# Sheet2.net
KiCad netlist of a schematic drawn in Altium Designer
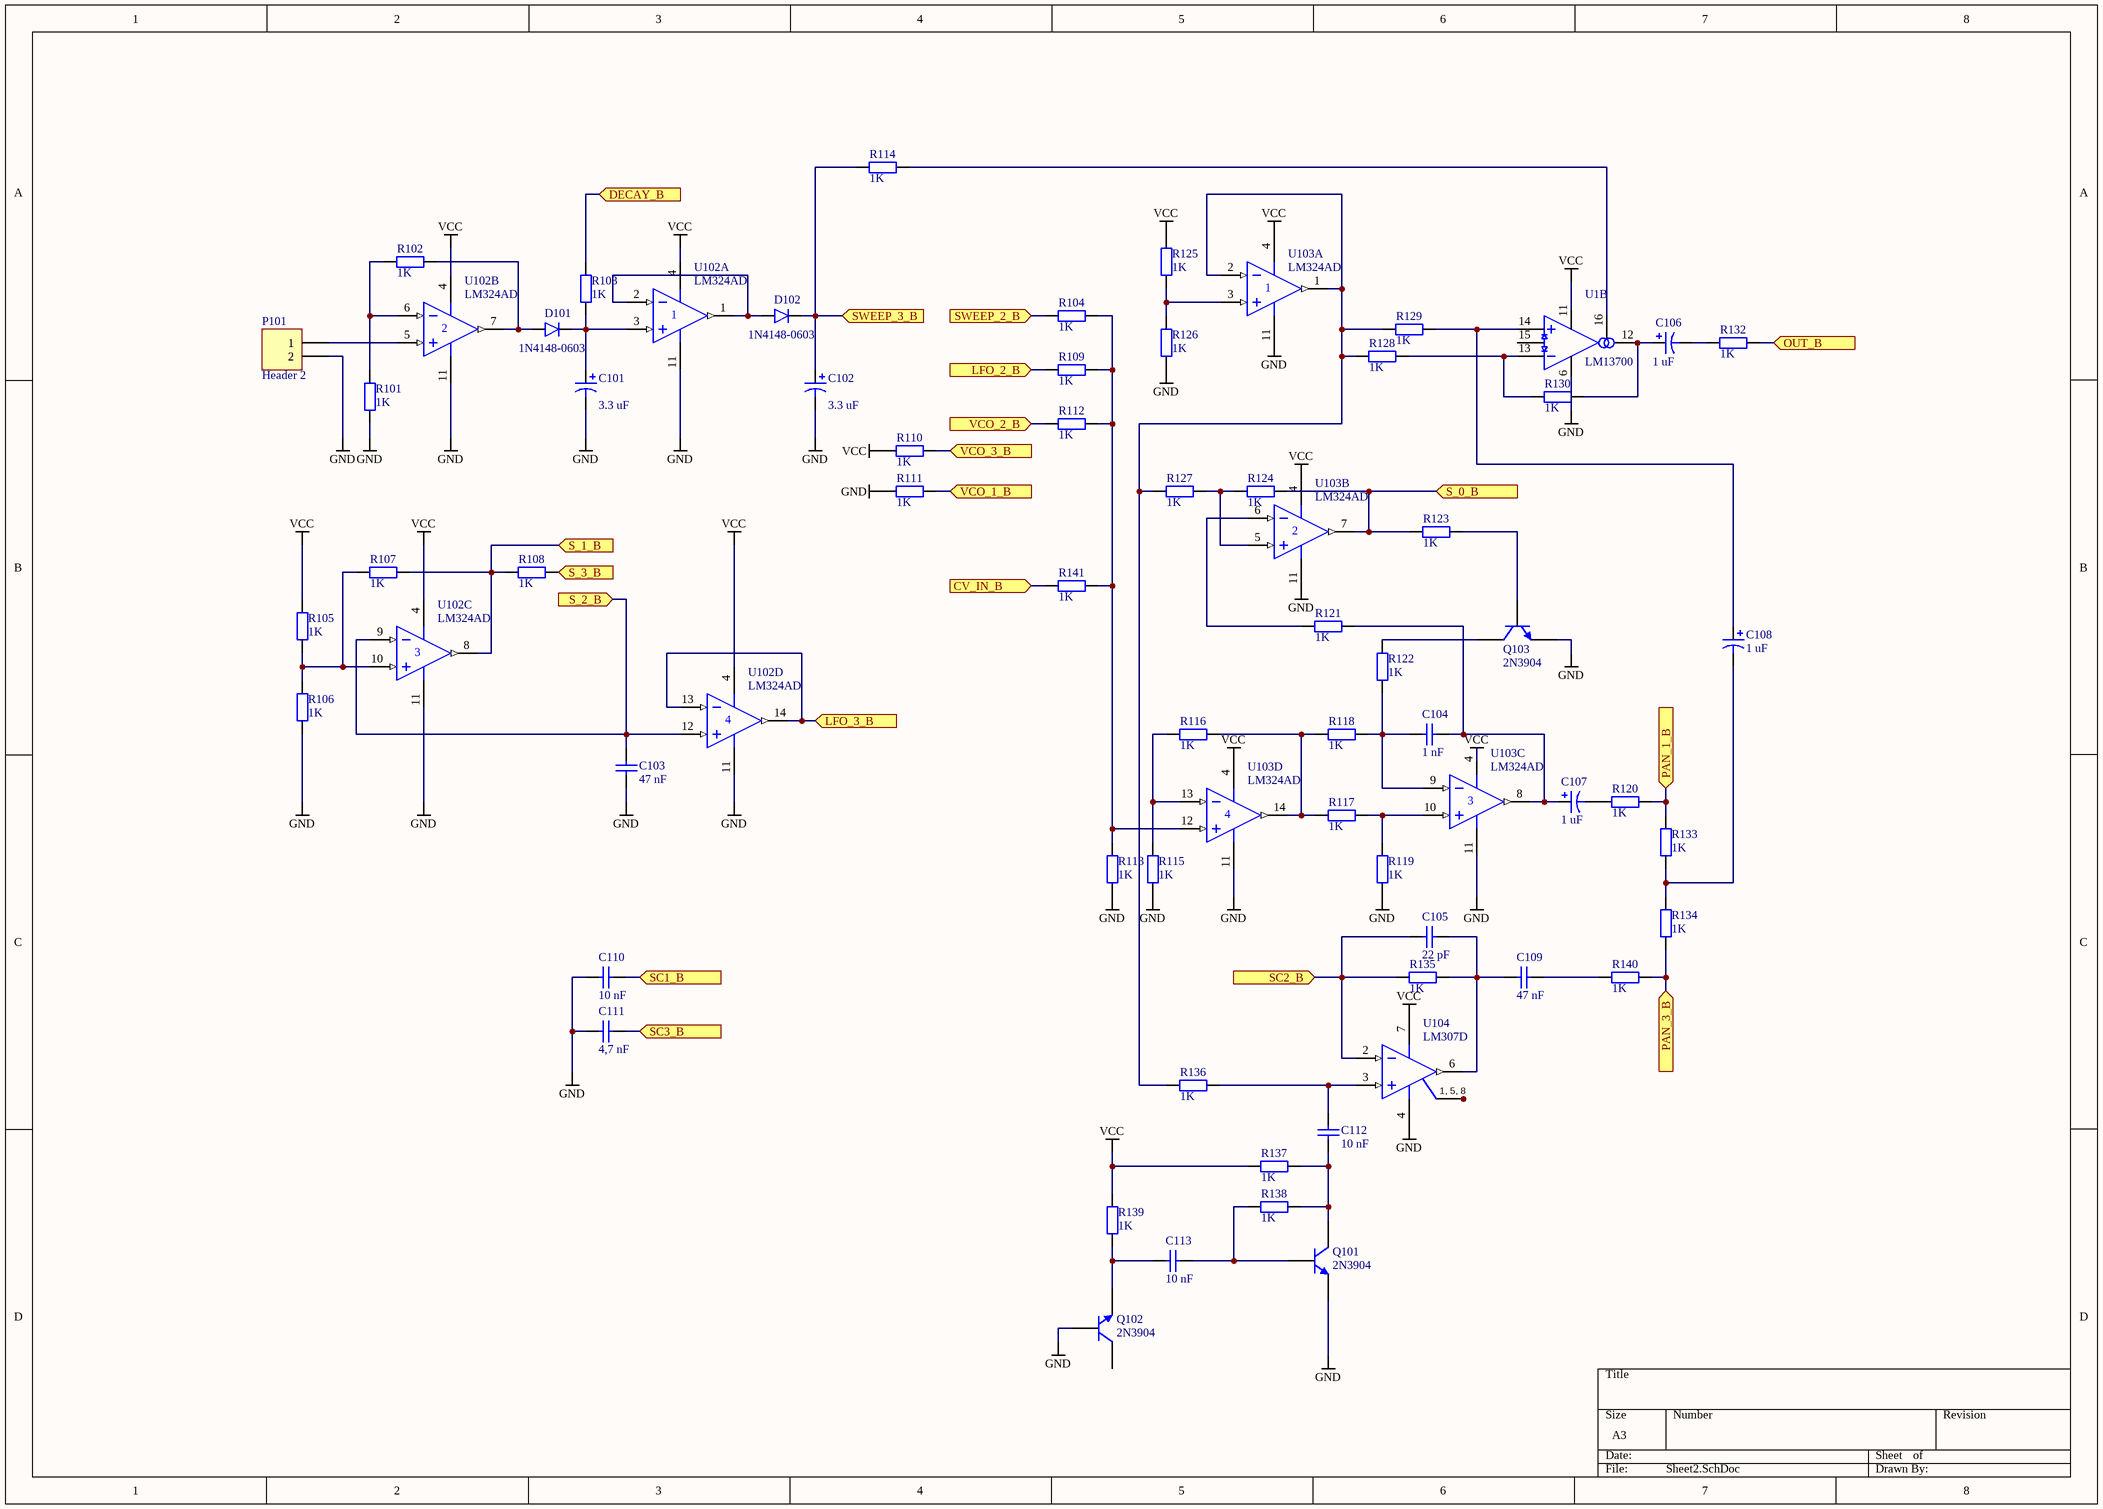
[diagram p0: Sheet2.SchDoc]

(export (version "E")
  (design (tool "Eeschema 10.0.6"))
  (components
    (comp (ref "C101")
      (value "3.3 uF")
      (footprint "C1206")
      (description "Polarized Capacitor (Radial)")
      (fields (field (name "Comment") "Cap Pol1") (field (name "PUBLISHER") "Altium Limited"))
      (libsource (lib "Miscellaneous Devices") (part "Cap Pol1"))
    )
    (comp (ref "C102")
      (value "3.3 uF")
      (footprint "C1206")
      (description "Polarized Capacitor (Radial)")
      (fields (field (name "Comment") "Cap Pol1") (field (name "PUBLISHER") "Altium Limited"))
      (libsource (lib "Miscellaneous Devices") (part "Cap Pol1"))
    )
    (comp (ref "C103")
      (value "47 nF")
      (footprint "C1206")
      (description "Capacitor")
      (fields (field (name "Comment") "Cap") (field (name "PUBLISHER") "Altium Limited"))
      (libsource (lib "Miscellaneous Devices") (part "Cap"))
    )
    (comp (ref "C104")
      (value "1 nF")
      (footprint "C1206")
      (description "Capacitor")
      (fields (field (name "Comment") "Cap") (field (name "PUBLISHER") "Altium Limited"))
      (libsource (lib "Miscellaneous Devices") (part "Cap"))
    )
    (comp (ref "C105")
      (value "22 pF")
      (footprint "C1206")
      (description "Capacitor")
      (fields (field (name "Comment") "Cap") (field (name "PUBLISHER") "Altium Limited"))
      (libsource (lib "Miscellaneous Devices") (part "Cap"))
    )
    (comp (ref "C106")
      (value "1 uF")
      (footprint "C1206")
      (description "Polarized Capacitor (Radial)")
      (fields (field (name "Comment") "Cap Pol1") (field (name "PUBLISHER") "Altium Limited"))
      (libsource (lib "Miscellaneous Devices") (part "Cap Pol1"))
    )
    (comp (ref "C107")
      (value "1 uF")
      (footprint "C1206")
      (description "Polarized Capacitor (Radial)")
      (fields (field (name "Comment") "Cap Pol1") (field (name "PUBLISHER") "Altium Limited"))
      (libsource (lib "Miscellaneous Devices") (part "Cap Pol1"))
    )
    (comp (ref "C108")
      (value "1 uF")
      (footprint "C1206")
      (description "Polarized Capacitor (Radial)")
      (fields (field (name "Comment") "Cap Pol1") (field (name "PUBLISHER") "Altium Limited"))
      (libsource (lib "Miscellaneous Devices") (part "Cap Pol1"))
    )
    (comp (ref "C109")
      (value "47 nF")
      (footprint "C1206")
      (description "Capacitor")
      (fields (field (name "Comment") "Cap") (field (name "PUBLISHER") "Altium Limited"))
      (libsource (lib "Miscellaneous Devices") (part "Cap"))
    )
    (comp (ref "C110")
      (value "10 nF")
      (footprint "C1206")
      (description "Capacitor")
      (fields (field (name "Comment") "Cap") (field (name "PUBLISHER") "Altium Limited"))
      (libsource (lib "Miscellaneous Devices") (part "Cap"))
    )
    (comp (ref "C111")
      (value "4,7 nF")
      (footprint "C1206")
      (description "Capacitor")
      (fields (field (name "Comment") "Cap") (field (name "PUBLISHER") "Altium Limited"))
      (libsource (lib "Miscellaneous Devices") (part "Cap"))
    )
    (comp (ref "C112")
      (value "10 nF")
      (footprint "C1206")
      (description "Capacitor")
      (fields (field (name "Comment") "Cap") (field (name "PUBLISHER") "Altium Limited"))
      (libsource (lib "Miscellaneous Devices") (part "Cap"))
    )
    (comp (ref "C113")
      (value "10 nF")
      (footprint "C1206")
      (description "Capacitor")
      (fields (field (name "Comment") "Cap") (field (name "PUBLISHER") "Altium Limited"))
      (libsource (lib "Miscellaneous Devices") (part "Cap"))
    )
    (comp (ref "D101")
      (value "1N4148-0603")
      (footprint "D0603")
      (description "Dioda: przełączająca; SMD; 100V; 150mA; 4ns; 0603")
      (libsource (lib "Component Library 3.0") (part "1N4148"))
    )
    (comp (ref "D102")
      (value "1N4148-0603")
      (footprint "D0603")
      (description "Dioda: przełączająca; SMD; 100V; 150mA; 4ns; 0603")
      (libsource (lib "Component Library 3.0") (part "1N4148"))
    )
    (comp (ref "P101")
      (value "Header 2")
      (footprint "HDR1X2")
      (description "Header, 2-Pin")
      (fields (field (name "PUBLISHER") "Altium Limited"))
      (libsource (lib "Miscellaneous Connectors") (part "Header 2"))
    )
    (comp (ref "Q101")
      (value "2N3904")
      (footprint "TO-92A")
      (description "NPN General Purpose Amplifier")
      (fields (field (name "PUBLISHER") "Altium Limited"))
      (libsource (lib "Miscellaneous Devices") (part "2N3904"))
    )
    (comp (ref "Q102")
      (value "2N3904")
      (footprint "TO-92A")
      (description "NPN General Purpose Amplifier")
      (fields (field (name "PUBLISHER") "Altium Limited"))
      (libsource (lib "Miscellaneous Devices") (part "2N3904"))
    )
    (comp (ref "Q103")
      (value "2N3904")
      (footprint "TO-92A")
      (description "NPN General Purpose Amplifier")
      (fields (field (name "PUBLISHER") "Altium Limited"))
      (libsource (lib "Miscellaneous Devices") (part "2N3904"))
    )
    (comp (ref "R101")
      (value "1K")
      (footprint "R1206")
      (description "Resistor")
      (fields (field (name "Comment") "Res2") (field (name "PUBLISHER") "Altium Limited"))
      (libsource (lib "Miscellaneous Devices") (part "Res2"))
    )
    (comp (ref "R102")
      (value "1K")
      (footprint "R1206")
      (description "Resistor")
      (fields (field (name "Comment") "Res2") (field (name "PUBLISHER") "Altium Limited"))
      (libsource (lib "") (part "Res2_1"))
    )
    (comp (ref "R103")
      (value "1K")
      (footprint "R1206")
      (description "Resistor")
      (fields (field (name "Comment") "Res2") (field (name "PUBLISHER") "Altium Limited"))
      (libsource (lib "") (part "Res2_3"))
    )
    (comp (ref "R104")
      (value "1K")
      (footprint "R1206")
      (description "Resistor")
      (fields (field (name "Comment") "Res2") (field (name "PUBLISHER") "Altium Limited"))
      (libsource (lib "") (part "Res2_2"))
    )
    (comp (ref "R105")
      (value "1K")
      (footprint "R1206")
      (description "Resistor")
      (fields (field (name "Comment") "Res2") (field (name "PUBLISHER") "Altium Limited"))
      (libsource (lib "Miscellaneous Devices") (part "Res2"))
    )
    (comp (ref "R106")
      (value "1K")
      (footprint "R1206")
      (description "Resistor")
      (fields (field (name "Comment") "Res2") (field (name "PUBLISHER") "Altium Limited"))
      (libsource (lib "Miscellaneous Devices") (part "Res2"))
    )
    (comp (ref "R107")
      (value "1K")
      (footprint "R1206")
      (description "Resistor")
      (fields (field (name "Comment") "Res2") (field (name "PUBLISHER") "Altium Limited"))
      (libsource (lib "") (part "Res2_1"))
    )
    (comp (ref "R108")
      (value "1K")
      (footprint "R1206")
      (description "Resistor")
      (fields (field (name "Comment") "Res2") (field (name "PUBLISHER") "Altium Limited"))
      (libsource (lib "") (part "Res2_1"))
    )
    (comp (ref "R109")
      (value "1K")
      (footprint "R1206")
      (description "Resistor")
      (fields (field (name "Comment") "Res2") (field (name "PUBLISHER") "Altium Limited"))
      (libsource (lib "") (part "Res2_1"))
    )
    (comp (ref "R110")
      (value "1K")
      (footprint "R1206")
      (description "Resistor")
      (fields (field (name "Comment") "Res2") (field (name "PUBLISHER") "Altium Limited"))
      (libsource (lib "") (part "Res2_2"))
    )
    (comp (ref "R111")
      (value "1K")
      (footprint "R1206")
      (description "Resistor")
      (fields (field (name "Comment") "Res2") (field (name "PUBLISHER") "Altium Limited"))
      (libsource (lib "") (part "Res2_1"))
    )
    (comp (ref "R112")
      (value "1K")
      (footprint "R1206")
      (description "Resistor")
      (fields (field (name "Comment") "Res2") (field (name "PUBLISHER") "Altium Limited"))
      (libsource (lib "") (part "Res2_1"))
    )
    (comp (ref "R113")
      (value "1K")
      (footprint "R1206")
      (description "Resistor")
      (fields (field (name "Comment") "Res2") (field (name "PUBLISHER") "Altium Limited"))
      (libsource (lib "") (part "Res2_3"))
    )
    (comp (ref "R114")
      (value "1K")
      (footprint "R1206")
      (description "Resistor")
      (fields (field (name "Comment") "Res2") (field (name "PUBLISHER") "Altium Limited"))
      (libsource (lib "") (part "Res2_2"))
    )
    (comp (ref "R115")
      (value "1K")
      (footprint "R1206")
      (description "Resistor")
      (fields (field (name "Comment") "Res2") (field (name "PUBLISHER") "Altium Limited"))
      (libsource (lib "Miscellaneous Devices") (part "Res2"))
    )
    (comp (ref "R116")
      (value "1K")
      (footprint "R1206")
      (description "Resistor")
      (fields (field (name "Comment") "Res2") (field (name "PUBLISHER") "Altium Limited"))
      (libsource (lib "") (part "Res2_1"))
    )
    (comp (ref "R117")
      (value "1K")
      (footprint "R1206")
      (description "Resistor")
      (fields (field (name "Comment") "Res2") (field (name "PUBLISHER") "Altium Limited"))
      (libsource (lib "") (part "Res2_1"))
    )
    (comp (ref "R118")
      (value "1K")
      (footprint "R1206")
      (description "Resistor")
      (fields (field (name "Comment") "Res2") (field (name "PUBLISHER") "Altium Limited"))
      (libsource (lib "") (part "Res2_1"))
    )
    (comp (ref "R119")
      (value "1K")
      (footprint "R1206")
      (description "Resistor")
      (fields (field (name "Comment") "Res2") (field (name "PUBLISHER") "Altium Limited"))
      (libsource (lib "") (part "Res2_3"))
    )
    (comp (ref "R120")
      (value "1K")
      (footprint "R1206")
      (description "Resistor")
      (fields (field (name "Comment") "Res2") (field (name "PUBLISHER") "Altium Limited"))
      (libsource (lib "") (part "Res2_2"))
    )
    (comp (ref "R121")
      (value "1K")
      (footprint "R1206")
      (description "Resistor")
      (fields (field (name "Comment") "Res2") (field (name "PUBLISHER") "Altium Limited"))
      (libsource (lib "") (part "Res2_2"))
    )
    (comp (ref "R122")
      (value "1K")
      (footprint "R1206")
      (description "Resistor")
      (fields (field (name "Comment") "Res2") (field (name "PUBLISHER") "Altium Limited"))
      (libsource (lib "Miscellaneous Devices") (part "Res2"))
    )
    (comp (ref "R123")
      (value "1K")
      (footprint "R1206")
      (description "Resistor")
      (fields (field (name "Comment") "Res2") (field (name "PUBLISHER") "Altium Limited"))
      (libsource (lib "") (part "Res2_1"))
    )
    (comp (ref "R124")
      (value "1K")
      (footprint "R1206")
      (description "Resistor")
      (fields (field (name "Comment") "Res2") (field (name "PUBLISHER") "Altium Limited"))
      (libsource (lib "") (part "Res2_1"))
    )
    (comp (ref "R125")
      (value "1K")
      (footprint "R1206")
      (description "Resistor")
      (fields (field (name "Comment") "Res2") (field (name "PUBLISHER") "Altium Limited"))
      (libsource (lib "") (part "Res2_3"))
    )
    (comp (ref "R126")
      (value "1K")
      (footprint "R1206")
      (description "Resistor")
      (fields (field (name "Comment") "Res2") (field (name "PUBLISHER") "Altium Limited"))
      (libsource (lib "") (part "Res2_3"))
    )
    (comp (ref "R127")
      (value "1K")
      (footprint "R1206")
      (description "Resistor")
      (fields (field (name "Comment") "Res2") (field (name "PUBLISHER") "Altium Limited"))
      (libsource (lib "") (part "Res2_2"))
    )
    (comp (ref "R128")
      (value "1K")
      (footprint "R1206")
      (description "Resistor")
      (fields (field (name "Comment") "Res2") (field (name "PUBLISHER") "Altium Limited"))
      (libsource (lib "") (part "Res2_2"))
    )
    (comp (ref "R129")
      (value "1K")
      (footprint "R1206")
      (description "Resistor")
      (fields (field (name "Comment") "Res2") (field (name "PUBLISHER") "Altium Limited"))
      (libsource (lib "") (part "Res2_2"))
    )
    (comp (ref "R130")
      (value "1K")
      (footprint "R1206")
      (description "Resistor")
      (fields (field (name "Comment") "Res2") (field (name "PUBLISHER") "Altium Limited"))
      (libsource (lib "") (part "Res2_2"))
    )
    (comp (ref "R132")
      (value "1K")
      (footprint "R1206")
      (description "Resistor")
      (fields (field (name "Comment") "Res2") (field (name "PUBLISHER") "Altium Limited"))
      (libsource (lib "") (part "Res2_2"))
    )
    (comp (ref "R133")
      (value "1K")
      (footprint "R1206")
      (description "Resistor")
      (fields (field (name "Comment") "Res2") (field (name "PUBLISHER") "Altium Limited"))
      (libsource (lib "Miscellaneous Devices") (part "Res2"))
    )
    (comp (ref "R134")
      (value "1K")
      (footprint "R1206")
      (description "Resistor")
      (fields (field (name "Comment") "Res2") (field (name "PUBLISHER") "Altium Limited"))
      (libsource (lib "Miscellaneous Devices") (part "Res2"))
    )
    (comp (ref "R135")
      (value "1K")
      (footprint "R1206")
      (description "Resistor")
      (fields (field (name "Comment") "Res2") (field (name "PUBLISHER") "Altium Limited"))
      (libsource (lib "") (part "Res2_1"))
    )
    (comp (ref "R136")
      (value "1K")
      (footprint "R1206")
      (description "Resistor")
      (fields (field (name "Comment") "Res2") (field (name "PUBLISHER") "Altium Limited"))
      (libsource (lib "") (part "Res2_1"))
    )
    (comp (ref "R137")
      (value "1K")
      (footprint "R1206")
      (description "Resistor")
      (fields (field (name "Comment") "Res2") (field (name "PUBLISHER") "Altium Limited"))
      (libsource (lib "") (part "Res2_1"))
    )
    (comp (ref "R138")
      (value "1K")
      (footprint "R1206")
      (description "Resistor")
      (fields (field (name "Comment") "Res2") (field (name "PUBLISHER") "Altium Limited"))
      (libsource (lib "") (part "Res2_1"))
    )
    (comp (ref "R139")
      (value "1K")
      (footprint "R1206")
      (description "Resistor")
      (fields (field (name "Comment") "Res2") (field (name "PUBLISHER") "Altium Limited"))
      (libsource (lib "") (part "Res2_3"))
    )
    (comp (ref "R140")
      (value "1K")
      (footprint "R1206")
      (description "Resistor")
      (fields (field (name "Comment") "Res2") (field (name "PUBLISHER") "Altium Limited"))
      (libsource (lib "") (part "Res2_2"))
    )
    (comp (ref "R141")
      (value "1K")
      (footprint "R1206")
      (description "Resistor")
      (fields (field (name "Comment") "Res2") (field (name "PUBLISHER") "Altium Limited"))
      (libsource (lib "") (part "Res2_2"))
    )
    (comp (ref "U1") (value "LM13700") (footprint "SOIC16") (libsource (lib "Schlib1") (part "LM13700")))
    (comp (ref "U102")
      (value "LM324AD")
      (footprint "D014_N")
      (description "Quadruple Operational Amplifier")
      (fields (field (name "PUBLISHER") "Altium Limited"))
      (libsource (lib "TI Operational Amplifier") (part "LM324AD"))
    )
    (comp (ref "U103")
      (value "LM324AD")
      (footprint "D014_N")
      (description "Quadruple Operational Amplifier")
      (fields (field (name "PUBLISHER") "Altium Limited"))
      (libsource (lib "TI Operational Amplifier") (part "LM324AD"))
    )
    (comp (ref "U104")
      (value "LM307D")
      (footprint "D008_L")
      (description "High-Performance Operational Amplifier")
      (fields (field (name "PUBLISHER") "Altium Limited"))
      (libsource (lib "TI Operational Amplifier") (part "LM307D"))
    )
  )
  (nets
    (net (code "1") (name "/CV_IN_B") (class "Default")
      (node (ref "R141") (pin "1") (pinfunction "1_1") (pintype "passive"))
    )
    (net (code "2") (name "/DECAY_B") (class "Default")
      (node (ref "R103") (pin "1") (pinfunction "1_1") (pintype "passive"))
    )
    (net (code "3") (name "/LFO_2_B") (class "Default")
      (node (ref "R109") (pin "2") (pinfunction "2_2") (pintype "passive"))
    )
    (net (code "4") (name "/LFO_3_B") (class "Default")
      (node (ref "U102") (pin "13") (pinfunction "IN-_13") (pintype "input"))
      (node (ref "U102") (pin "14") (pinfunction "OUT_14") (pintype "output"))
    )
    (net (code "5") (name "/OUT_B") (class "Default")
      (node (ref "R132") (pin "2") (pinfunction "2_2") (pintype "passive"))
    )
    (net (code "6") (name "/PAN_1_B") (class "Default")
      (node (ref "R120") (pin "2") (pinfunction "2_2") (pintype "passive"))
      (node (ref "R133") (pin "2") (pinfunction "2_2") (pintype "passive"))
    )
    (net (code "7") (name "/PAN_3_B") (class "Default")
      (node (ref "R134") (pin "1") (pinfunction "1_1") (pintype "passive"))
      (node (ref "R140") (pin "2") (pinfunction "2_2") (pintype "passive"))
    )
    (net (code "8") (name "/SC1_B") (class "Default")
      (node (ref "C110") (pin "1") (pinfunction "1_1") (pintype "passive"))
    )
    (net (code "9") (name "/SC2_B") (class "Default")
      (node (ref "C105") (pin "2") (pinfunction "2_2") (pintype "passive"))
      (node (ref "R135") (pin "2") (pinfunction "2_2") (pintype "passive"))
      (node (ref "U104") (pin "2") (pinfunction "IN-_2") (pintype "input"))
    )
    (net (code "10") (name "/SC3_B") (class "Default")
      (node (ref "C111") (pin "1") (pinfunction "1_1") (pintype "passive"))
    )
    (net (code "11") (name "/SWEEP_2_B") (class "Default")
      (node (ref "R104") (pin "1") (pinfunction "1_1") (pintype "passive"))
    )
    (net (code "12") (name "/SWEEP_3_B") (class "Default")
      (node (ref "C102") (pin "1") (pinfunction "1_1") (pintype "passive"))
      (node (ref "D102") (pin "1") (pinfunction "1_1") (pintype "passive"))
      (node (ref "R114") (pin "1") (pinfunction "1_1") (pintype "passive"))
    )
    (net (code "13") (name "/S_0_B") (class "Default")
      (node (ref "R123") (pin "2") (pinfunction "2_2") (pintype "passive"))
      (node (ref "R124") (pin "1") (pinfunction "1_1") (pintype "passive"))
      (node (ref "U103") (pin "7") (pinfunction "OUT_7") (pintype "output"))
    )
    (net (code "14") (name "/S_1_B") (class "Default")
      (node (ref "R107") (pin "1") (pinfunction "1_1") (pintype "passive"))
      (node (ref "R108") (pin "2") (pinfunction "2_2") (pintype "passive"))
      (node (ref "U102") (pin "8") (pinfunction "OUT_8") (pintype "output"))
    )
    (net (code "15") (name "/S_2_B") (class "Default")
      (node (ref "C103") (pin "2") (pinfunction "2_2") (pintype "passive"))
      (node (ref "U102") (pin "12") (pinfunction "IN+_12") (pintype "input"))
      (node (ref "U102") (pin "9") (pinfunction "IN-_9") (pintype "input"))
    )
    (net (code "16") (name "/S_3_B") (class "Default")
      (node (ref "R108") (pin "1") (pinfunction "1_1") (pintype "passive"))
    )
    (net (code "17") (name "/VCO_1_B") (class "Default")
      (node (ref "R111") (pin "1") (pinfunction "1_1") (pintype "passive"))
    )
    (net (code "18") (name "/VCO_2_B") (class "Default")
      (node (ref "R112") (pin "2") (pinfunction "2_2") (pintype "passive"))
    )
    (net (code "19") (name "/VCO_3_B") (class "Default")
      (node (ref "R110") (pin "2") (pinfunction "2_2") (pintype "passive"))
    )
    (net (code "20") (name "GND") (class "Default")
      (node (ref "C101") (pin "2") (pinfunction "2_2") (pintype "passive"))
      (node (ref "C102") (pin "2") (pinfunction "2_2") (pintype "passive"))
      (node (ref "C103") (pin "1") (pinfunction "1_1") (pintype "passive"))
      (node (ref "C110") (pin "2") (pinfunction "2_2") (pintype "passive"))
      (node (ref "C111") (pin "2") (pinfunction "2_2") (pintype "passive"))
      (node (ref "P101") (pin "2") (pinfunction "2_2") (pintype "passive"))
      (node (ref "Q101") (pin "1") (pinfunction "E_1") (pintype "passive"))
      (node (ref "Q102") (pin "2") (pinfunction "B_2") (pintype "passive"))
      (node (ref "Q103") (pin "1") (pinfunction "E_1") (pintype "passive"))
      (node (ref "R101") (pin "1") (pinfunction "1_1") (pintype "passive"))
      (node (ref "R106") (pin "1") (pinfunction "1_1") (pintype "passive"))
      (node (ref "R111") (pin "2") (pinfunction "2_2") (pintype "passive"))
      (node (ref "R113") (pin "2") (pinfunction "2_2") (pintype "passive"))
      (node (ref "R115") (pin "1") (pinfunction "1_1") (pintype "passive"))
      (node (ref "R119") (pin "2") (pinfunction "2_2") (pintype "passive"))
      (node (ref "R126") (pin "2") (pinfunction "2_2") (pintype "passive"))
      (node (ref "U1") (pin "6") (pinfunction "V-_6") (pintype "passive"))
      (node (ref "U102") (pin "11") (pinfunction "V-_11") (pintype "power_in"))
      (node (ref "U103") (pin "11") (pinfunction "V-_11") (pintype "power_in"))
      (node (ref "U104") (pin "4") (pinfunction "V-_4") (pintype "power_in"))
    )
    (net (code "21") (name "Net-(C106-Pad1)") (class "Default")
      (node (ref "C106") (pin "1") (pinfunction "1_1") (pintype "passive"))
      (node (ref "R130") (pin "2") (pinfunction "2_2") (pintype "passive"))
      (node (ref "U1") (pin "12") (pinfunction "amp_bias_12") (pintype "passive"))
    )
    (net (code "22") (name "Net-(C106-Pad2)") (class "Default")
      (node (ref "C106") (pin "2") (pinfunction "2_2") (pintype "passive"))
      (node (ref "R132") (pin "1") (pinfunction "1_1") (pintype "passive"))
    )
    (net (code "23") (name "Net-(C107-Pad2)") (class "Default")
      (node (ref "C107") (pin "2") (pinfunction "2_2") (pintype "passive"))
      (node (ref "R120") (pin "1") (pinfunction "1_1") (pintype "passive"))
    )
    (net (code "24") (name "Net-(C108-Pad2)") (class "Default")
      (node (ref "C108") (pin "2") (pinfunction "2_2") (pintype "passive"))
      (node (ref "R133") (pin "1") (pinfunction "1_1") (pintype "passive"))
      (node (ref "R134") (pin "2") (pinfunction "2_2") (pintype "passive"))
    )
    (net (code "25") (name "Net-(C109-Pad2)") (class "Default")
      (node (ref "C109") (pin "2") (pinfunction "2_2") (pintype "passive"))
      (node (ref "R140") (pin "1") (pinfunction "1_1") (pintype "passive"))
    )
    (net (code "26") (name "Net-(Q101-B)") (class "Default")
      (node (ref "C113") (pin "2") (pinfunction "2_2") (pintype "passive"))
      (node (ref "Q101") (pin "2") (pinfunction "B_2") (pintype "passive"))
      (node (ref "R138") (pin "2") (pinfunction "2_2") (pintype "passive"))
    )
    (net (code "27") (name "Net-(Q101-C)") (class "Default")
      (node (ref "C112") (pin "2") (pinfunction "2_2") (pintype "passive"))
      (node (ref "Q101") (pin "3") (pinfunction "C_3") (pintype "passive"))
      (node (ref "R137") (pin "1") (pinfunction "1_1") (pintype "passive"))
      (node (ref "R138") (pin "1") (pinfunction "1_1") (pintype "passive"))
    )
    (net (code "28") (name "Net-(Q102-E)") (class "Default")
      (node (ref "C113") (pin "1") (pinfunction "1_1") (pintype "passive"))
      (node (ref "Q102") (pin "1") (pinfunction "E_1") (pintype "passive"))
      (node (ref "R139") (pin "2") (pinfunction "2_2") (pintype "passive"))
    )
    (net (code "29") (name "Net-(Q103-B)") (class "Default")
      (node (ref "Q103") (pin "2") (pinfunction "B_2") (pintype "passive"))
      (node (ref "R123") (pin "1") (pinfunction "1_1") (pintype "passive"))
    )
    (net (code "30") (name "Net-(Q103-C)") (class "Default")
      (node (ref "Q103") (pin "3") (pinfunction "C_3") (pintype "passive"))
      (node (ref "R122") (pin "2") (pinfunction "2_2") (pintype "passive"))
    )
    (net (code "31") (name "Net-(R114-Pad2)") (class "Default")
      (node (ref "R114") (pin "2") (pinfunction "2_2") (pintype "passive"))
      (node (ref "U1") (pin "16") (pinfunction "amp_bias_16") (pintype "passive"))
    )
    (net (code "32") (name "Net-(R128-Pad2)") (class "Default")
      (node (ref "R128") (pin "2") (pinfunction "2_2") (pintype "passive"))
      (node (ref "R130") (pin "1") (pinfunction "1_1") (pintype "passive"))
      (node (ref "U1") (pin "13") (pinfunction "amp_bias_13") (pintype "passive"))
    )
    (net (code "33") (name "Net-(U1B-+)") (class "Default")
      (node (ref "C108") (pin "1") (pinfunction "1_1") (pintype "passive"))
      (node (ref "R129") (pin "2") (pinfunction "2_2") (pintype "passive"))
      (node (ref "U1") (pin "14") (pinfunction "+_14") (pintype "passive"))
    )
    (net (code "34") (name "Net-(U102A-IN+)") (class "Default")
      (node (ref "C101") (pin "1") (pinfunction "1_1") (pintype "passive"))
      (node (ref "D101") (pin "1") (pinfunction "1_1") (pintype "passive"))
      (node (ref "R103") (pin "2") (pinfunction "2_2") (pintype "passive"))
      (node (ref "U102") (pin "3") (pinfunction "IN+_3") (pintype "input"))
    )
    (net (code "35") (name "Net-(U102A-IN-)") (class "Default")
      (node (ref "D102") (pin "2") (pinfunction "2_2") (pintype "passive"))
      (node (ref "U102") (pin "1") (pinfunction "OUT_1") (pintype "output"))
      (node (ref "U102") (pin "2") (pinfunction "IN-_2") (pintype "input"))
    )
    (net (code "36") (name "Net-(U102B-IN+)") (class "Default")
      (node (ref "P101") (pin "1") (pinfunction "1_1") (pintype "passive"))
      (node (ref "U102") (pin "5") (pinfunction "IN+_5") (pintype "input"))
    )
    (net (code "37") (name "Net-(U102B-IN-)") (class "Default")
      (node (ref "R101") (pin "2") (pinfunction "2_2") (pintype "passive"))
      (node (ref "R102") (pin "2") (pinfunction "2_2") (pintype "passive"))
      (node (ref "U102") (pin "6") (pinfunction "IN-_6") (pintype "input"))
    )
    (net (code "38") (name "Net-(U102B-OUT)") (class "Default")
      (node (ref "D101") (pin "2") (pinfunction "2_2") (pintype "passive"))
      (node (ref "R102") (pin "1") (pinfunction "1_1") (pintype "passive"))
      (node (ref "U102") (pin "7") (pinfunction "OUT_7") (pintype "output"))
    )
    (net (code "39") (name "Net-(U102C-IN+)") (class "Default")
      (node (ref "R105") (pin "1") (pinfunction "1_1") (pintype "passive"))
      (node (ref "R106") (pin "2") (pinfunction "2_2") (pintype "passive"))
      (node (ref "R107") (pin "2") (pinfunction "2_2") (pintype "passive"))
      (node (ref "U102") (pin "10") (pinfunction "IN+_10") (pintype "input"))
    )
    (net (code "40") (name "Net-(U103A-IN+)") (class "Default")
      (node (ref "R125") (pin "2") (pinfunction "2_2") (pintype "passive"))
      (node (ref "R126") (pin "1") (pinfunction "1_1") (pintype "passive"))
      (node (ref "U103") (pin "3") (pinfunction "IN+_3") (pintype "input"))
    )
    (net (code "41") (name "Net-(U103A-IN-)") (class "Default")
      (node (ref "R127") (pin "1") (pinfunction "1_1") (pintype "passive"))
      (node (ref "R128") (pin "1") (pinfunction "1_1") (pintype "passive"))
      (node (ref "R129") (pin "1") (pinfunction "1_1") (pintype "passive"))
      (node (ref "R136") (pin "2") (pinfunction "2_2") (pintype "passive"))
      (node (ref "U103") (pin "1") (pinfunction "OUT_1") (pintype "output"))
      (node (ref "U103") (pin "2") (pinfunction "IN-_2") (pintype "input"))
    )
    (net (code "42") (name "Net-(U103B-IN+)") (class "Default")
      (node (ref "R124") (pin "2") (pinfunction "2_2") (pintype "passive"))
      (node (ref "R127") (pin "2") (pinfunction "2_2") (pintype "passive"))
      (node (ref "U103") (pin "5") (pinfunction "IN+_5") (pintype "input"))
    )
    (net (code "43") (name "Net-(U103B-IN-)") (class "Default")
      (node (ref "R121") (pin "1") (pinfunction "1_1") (pintype "passive"))
      (node (ref "U103") (pin "6") (pinfunction "IN-_6") (pintype "input"))
    )
    (net (code "44") (name "Net-(U103C-IN+)") (class "Default")
      (node (ref "R117") (pin "1") (pinfunction "1_1") (pintype "passive"))
      (node (ref "R119") (pin "1") (pinfunction "1_1") (pintype "passive"))
      (node (ref "U103") (pin "10") (pinfunction "IN+_10") (pintype "input"))
    )
    (net (code "45") (name "Net-(U103C-IN-)") (class "Default")
      (node (ref "C104") (pin "2") (pinfunction "2_2") (pintype "passive"))
      (node (ref "R118") (pin "1") (pinfunction "1_1") (pintype "passive"))
      (node (ref "R122") (pin "1") (pinfunction "1_1") (pintype "passive"))
      (node (ref "U103") (pin "9") (pinfunction "IN-_9") (pintype "input"))
    )
    (net (code "46") (name "Net-(U103C-OUT)") (class "Default")
      (node (ref "C104") (pin "1") (pinfunction "1_1") (pintype "passive"))
      (node (ref "C107") (pin "1") (pinfunction "1_1") (pintype "passive"))
      (node (ref "R121") (pin "2") (pinfunction "2_2") (pintype "passive"))
      (node (ref "U103") (pin "8") (pinfunction "OUT_8") (pintype "output"))
    )
    (net (code "47") (name "Net-(U103D-IN+)") (class "Default")
      (node (ref "R104") (pin "2") (pinfunction "2_2") (pintype "passive"))
      (node (ref "R109") (pin "1") (pinfunction "1_1") (pintype "passive"))
      (node (ref "R112") (pin "1") (pinfunction "1_1") (pintype "passive"))
      (node (ref "R113") (pin "1") (pinfunction "1_1") (pintype "passive"))
      (node (ref "R141") (pin "2") (pinfunction "2_2") (pintype "passive"))
      (node (ref "U103") (pin "12") (pinfunction "IN+_12") (pintype "input"))
    )
    (net (code "48") (name "Net-(U103D-IN-)") (class "Default")
      (node (ref "R115") (pin "2") (pinfunction "2_2") (pintype "passive"))
      (node (ref "R116") (pin "2") (pinfunction "2_2") (pintype "passive"))
      (node (ref "U103") (pin "13") (pinfunction "IN-_13") (pintype "input"))
    )
    (net (code "49") (name "Net-(U103D-OUT)") (class "Default")
      (node (ref "R116") (pin "1") (pinfunction "1_1") (pintype "passive"))
      (node (ref "R117") (pin "2") (pinfunction "2_2") (pintype "passive"))
      (node (ref "R118") (pin "2") (pinfunction "2_2") (pintype "passive"))
      (node (ref "U103") (pin "14") (pinfunction "OUT_14") (pintype "output"))
    )
    (net (code "50") (name "Net-(U104-IN+)") (class "Default")
      (node (ref "C112") (pin "1") (pinfunction "1_1") (pintype "passive"))
      (node (ref "R136") (pin "1") (pinfunction "1_1") (pintype "passive"))
      (node (ref "U104") (pin "3") (pinfunction "IN+_3") (pintype "input"))
    )
    (net (code "51") (name "Net-(U104-NC-Pad1)") (class "Default")
      (node (ref "U104") (pin "1") (pinfunction "NC_1") (pintype "passive"))
      (node (ref "U104") (pin "5") (pinfunction "NC_5") (pintype "passive"))
      (node (ref "U104") (pin "8") (pinfunction "NC_8") (pintype "passive"))
    )
    (net (code "52") (name "Net-(U104-OUT)") (class "Default")
      (node (ref "C105") (pin "1") (pinfunction "1_1") (pintype "passive"))
      (node (ref "C109") (pin "1") (pinfunction "1_1") (pintype "passive"))
      (node (ref "R135") (pin "1") (pinfunction "1_1") (pintype "passive"))
      (node (ref "U104") (pin "6") (pinfunction "OUT_6") (pintype "output"))
    )
    (net (code "53") (name "VCC") (class "Default")
      (node (ref "R105") (pin "2") (pinfunction "2_2") (pintype "passive"))
      (node (ref "R110") (pin "1") (pinfunction "1_1") (pintype "passive"))
      (node (ref "R125") (pin "1") (pinfunction "1_1") (pintype "passive"))
      (node (ref "R137") (pin "2") (pinfunction "2_2") (pintype "passive"))
      (node (ref "R139") (pin "1") (pinfunction "1_1") (pintype "passive"))
      (node (ref "U1") (pin "11") (pinfunction "V+_11") (pintype "passive"))
      (node (ref "U102") (pin "4") (pinfunction "V+_4") (pintype "power_in"))
      (node (ref "U103") (pin "4") (pinfunction "V+_4") (pintype "power_in"))
      (node (ref "U104") (pin "7") (pinfunction "V+_7") (pintype "power_in"))
    )
    (net (code "54") (name "unconnected-(Q102-C-Pad3)") (class "Default")
      (node (ref "Q102") (pin "3") (pinfunction "C_3") (pintype "passive"))
    )
    (net (code "55") (name "unconnected-(U1B-amp_bias-Pad15)") (class "Default")
      (node (ref "U1") (pin "15") (pinfunction "amp_bias_15") (pintype "passive"))
    )
  )
)
